# Power.net
KiCad netlist of a schematic drawn in Altium Designer
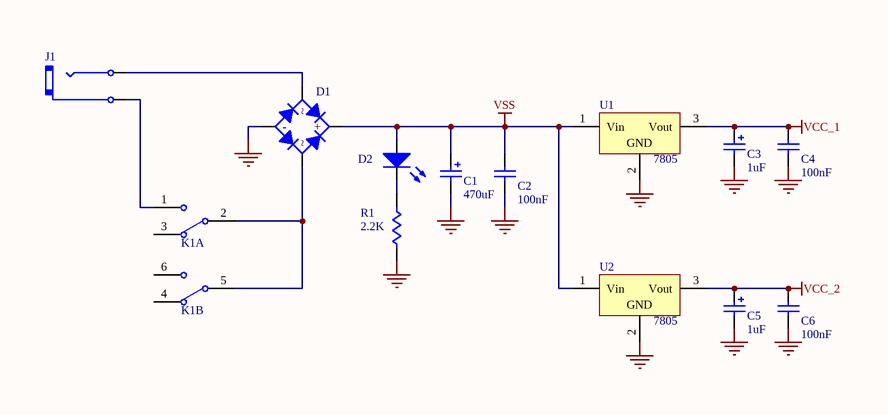
[diagram p0: Power.SchDoc]

(export (version "E")
  (design (tool "Eeschema 10.0.6"))
  (components
    (comp (ref "C1")
      (value "470uF")
      (footprint "RB_3.175mm")
      (description "Polarized Capacitor (Radial)")
      (fields
        (field (name "MANUFACTURER") "Generic Components")
        (field (name "Comment") "Capacitor_1")
        (field (name "PUBLISHER") "Altium Limited")
      )
      (libsource (lib "my Libraries") (part "Capacitor_1"))
    )
    (comp (ref "C2")
      (value "100nF")
      (footprint "RAD_5.08MM")
      (description "Polarized Capacitor (Radial)")
      (fields
        (field (name "MANUFACTURER") "Generic Components")
        (field (name "Comment") "Capacitor_2")
        (field (name "PUBLISHER") "Altium Limited")
      )
      (libsource (lib "my Libraries") (part "Capacitor_2"))
    )
    (comp (ref "C3")
      (value "1uF")
      (footprint "RB_3.175mm")
      (description "Polarized Capacitor (Radial)")
      (fields
        (field (name "MANUFACTURER") "Generic Components")
        (field (name "Comment") "Capacitor_1")
        (field (name "PUBLISHER") "Altium Limited")
      )
      (libsource (lib "my Libraries") (part "Capacitor_1"))
    )
    (comp (ref "C4")
      (value "100nF")
      (footprint "RAD_5.08MM")
      (description "Polarized Capacitor (Radial)")
      (fields
        (field (name "MANUFACTURER") "Generic Components")
        (field (name "Comment") "Capacitor_2")
        (field (name "PUBLISHER") "Altium Limited")
      )
      (libsource (lib "my Libraries") (part "Capacitor_2"))
    )
    (comp (ref "C5")
      (value "1uF")
      (footprint "RB_3.175mm")
      (description "Polarized Capacitor (Radial)")
      (fields
        (field (name "MANUFACTURER") "Generic Components")
        (field (name "Comment") "Capacitor_1")
        (field (name "PUBLISHER") "Altium Limited")
      )
      (libsource (lib "my Libraries") (part "Capacitor_1"))
    )
    (comp (ref "C6")
      (value "100nF")
      (footprint "RAD_5.08MM")
      (description "Polarized Capacitor (Radial)")
      (fields
        (field (name "MANUFACTURER") "Generic Components")
        (field (name "Comment") "Capacitor_2")
        (field (name "PUBLISHER") "Altium Limited")
      )
      (libsource (lib "my Libraries") (part "Capacitor_2"))
    )
    (comp (ref "D1")
      (value "Bridge")
      (footprint "Bridg_2A")
      (description "Full Wave Diode Bridge")
      (fields (field (name "MANUFACTURER") "Generic Components") (field (name "PUBLISHER") "Altium Limited"))
      (libsource (lib "my Libraries") (part "Bridge"))
    )
    (comp (ref "D2")
      (value "Optical Transmitter")
      (footprint "LED_5mm")
      (description "Typical INFRARED GaAs LED")
      (fields (field (name "MANUFACTURER") "Generic Components") (field (name "PUBLISHER") "Altium Limited"))
      (libsource (lib "my Libraries") (part "Optical Transmitter"))
    )
    (comp (ref "J1")
      (value "Jack_Power")
      (footprint "Jack_Power")
      (description "2-Conductor Jack")
      (fields (field (name "MANUFACTURER") "Generic Components") (field (name "PUBLISHER") "Altium Limited"))
      (libsource (lib "my Libraries") (part "Jack_Power"))
    )
    (comp (ref "K1")
      (value "SW-SPDT")
      (footprint "KEY ON/OFF 6PIN")
      (description "Single-Pole, Double-Throw Switch, Key")
      (fields (field (name "MANUFACTURER") "Generic Components") (field (name "PUBLISHER") "Altium Limited"))
      (libsource (lib "") (part "SW-SPDT_1"))
    )
    (comp (ref "R1")
      (value "2.2K")
      (footprint "AXIAL0.4")
      (description "Thermistor")
      (fields
        (field (name "MANUFACTURER") "Generic Components")
        (field (name "Comment") "Resistor")
        (field (name "PUBLISHER") "Altium Limited")
      )
      (libsource (lib "my Libraries") (part "Resistor"))
    )
    (comp (ref "U1")
      (value "7805")
      (footprint "TO257H")
      (description "Voltage Regulator")
      (fields
        (field (name "MANUFACTURER") "Generic Components")
        (field (name "Comment") "Volt Reg")
        (field (name "PUBLISHER") "Altium Limited")
      )
      (libsource (lib "my Libraries") (part "Volt Reg"))
    )
    (comp (ref "U2")
      (value "7805")
      (footprint "TO257H")
      (description "Voltage Regulator")
      (fields
        (field (name "MANUFACTURER") "Generic Components")
        (field (name "Comment") "Volt Reg")
        (field (name "PUBLISHER") "Altium Limited")
      )
      (libsource (lib "my Libraries") (part "Volt Reg"))
    )
  )
  (nets
    (net (code "1") (name "GND") (class "Default")
      (node (ref "C1") (pin "2") (pinfunction "2_2") (pintype "passive"))
      (node (ref "C2") (pin "2") (pinfunction "2_2") (pintype "passive"))
      (node (ref "C3") (pin "2") (pinfunction "2_2") (pintype "passive"))
      (node (ref "C4") (pin "2") (pinfunction "2_2") (pintype "passive"))
      (node (ref "C5") (pin "2") (pinfunction "2_2") (pintype "passive"))
      (node (ref "C6") (pin "2") (pinfunction "2_2") (pintype "passive"))
      (node (ref "D1") (pin "1") (pinfunction "-_1") (pintype "passive"))
      (node (ref "R1") (pin "2") (pinfunction "2_2") (pintype "passive"))
      (node (ref "U1") (pin "2") (pinfunction "GND_2") (pintype "passive"))
      (node (ref "U2") (pin "2") (pinfunction "GND_2") (pintype "passive"))
    )
    (net (code "2") (name "Net-(D2-K)") (class "Default")
      (node (ref "D2") (pin "2") (pinfunction "K_2") (pintype "passive"))
      (node (ref "R1") (pin "1") (pinfunction "1_1") (pintype "passive"))
    )
    (net (code "3") (name "Net-(J1-A)") (class "Default")
      (node (ref "D1") (pin "4") (pinfunction "~_4") (pintype "passive"))
      (node (ref "J1") (pin "1") (pinfunction "A_1") (pintype "passive"))
    )
    (net (code "4") (name "Net-(J1-B)") (class "Default")
      (node (ref "J1") (pin "2") (pinfunction "B_2") (pintype "passive"))
      (node (ref "K1") (pin "1") (pinfunction "NO_1") (pintype "passive"))
    )
    (net (code "5") (name "Net-(K1A-COMMON)") (class "Default")
      (node (ref "D1") (pin "2") (pinfunction "~_2") (pintype "passive"))
      (node (ref "K1") (pin "2") (pinfunction "COMMON_2") (pintype "passive"))
      (node (ref "K1") (pin "5") (pinfunction "COMMON_5") (pintype "passive"))
    )
    (net (code "6") (name "VCC_1") (class "Default")
      (node (ref "C3") (pin "1") (pinfunction "1_1") (pintype "passive"))
      (node (ref "C4") (pin "1") (pinfunction "1_1") (pintype "passive"))
      (node (ref "U1") (pin "3") (pinfunction "Vout_3") (pintype "passive"))
    )
    (net (code "7") (name "VCC_2") (class "Default")
      (node (ref "C5") (pin "1") (pinfunction "1_1") (pintype "passive"))
      (node (ref "C6") (pin "1") (pinfunction "1_1") (pintype "passive"))
      (node (ref "U2") (pin "3") (pinfunction "Vout_3") (pintype "passive"))
    )
    (net (code "8") (name "VSS") (class "Default")
      (node (ref "C1") (pin "1") (pinfunction "1_1") (pintype "passive"))
      (node (ref "C2") (pin "1") (pinfunction "1_1") (pintype "passive"))
      (node (ref "D1") (pin "3") (pinfunction "+_3") (pintype "passive"))
      (node (ref "D2") (pin "1") (pinfunction "A_1") (pintype "passive"))
      (node (ref "U1") (pin "1") (pinfunction "Vin_1") (pintype "passive"))
      (node (ref "U2") (pin "1") (pinfunction "Vin_1") (pintype "passive"))
    )
    (net (code "9") (name "unconnected-(K1A-NC-Pad3)") (class "Default")
      (node (ref "K1") (pin "3") (pinfunction "NC_3") (pintype "passive"))
    )
    (net (code "10") (name "unconnected-(K1B-NC-Pad4)") (class "Default")
      (node (ref "K1") (pin "4") (pinfunction "NC_4") (pintype "passive"))
    )
    (net (code "11") (name "unconnected-(K1B-NO-Pad6)") (class "Default")
      (node (ref "K1") (pin "6") (pinfunction "NO_6") (pintype "passive"))
    )
  )
)
